# SH7_-_BROADCOM_ENCODER.net
KiCad netlist of a schematic drawn in Altium Designer
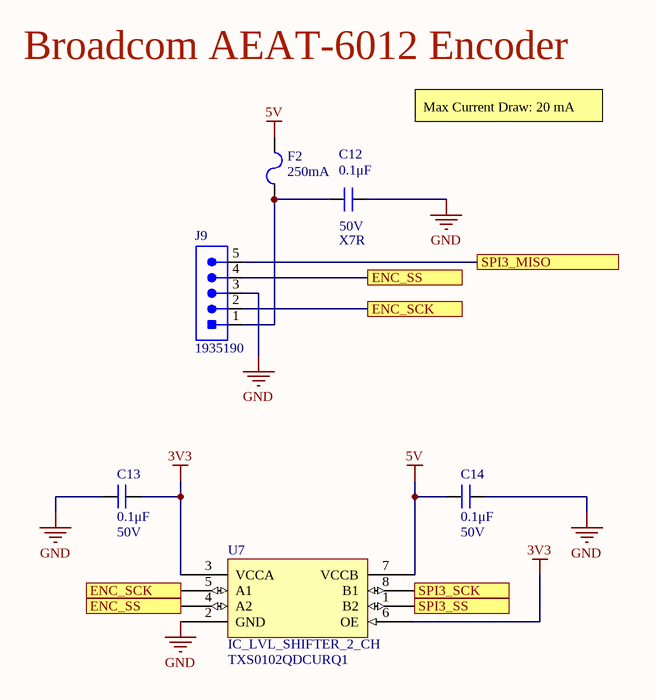
[diagram p0: SH7 - BROADCOM ENCODER.SchDoc]

(export (version "E")
  (design (tool "Eeschema 10.0.6"))
  (components
    (comp (ref "C12")
      (value "0.1μF")
      (footprint "CAP0603")
      (description "CAP CER 0.1UF 50V X7R 0603")
      (fields
        (field (name "DIELECTRIC") "X7R")
        (field (name "VOLTAGE RATING") "50V")
        (field (name "Comment") "CAP_0.1uF_50V_0603")
      )
      (libsource (lib "UWRT_Schematic_Library_2020") (part "CAP_0.1uF_50V_0603"))
    )
    (comp (ref "C13")
      (value "0.1μF")
      (footprint "CAP2012")
      (description "CAP CER 0.1UF 50V X7R 0805")
      (fields
        (field (name "LCSC PART #") "C49678")
        (field (name "VOLTAGE RATING") "50V")
        (field (name "Comment") "CAP_0.1uF_50V_0805")
      )
      (libsource (lib "UWRT_Schematic_Library_2020") (part "CAP_0.1uF_50V_0805"))
    )
    (comp (ref "C14")
      (value "0.1μF")
      (footprint "CAP2012")
      (description "CAP CER 0.1UF 50V X7R 0805")
      (fields
        (field (name "LCSC PART #") "C49678")
        (field (name "VOLTAGE RATING") "50V")
        (field (name "Comment") "CAP_0.1uF_50V_0805")
      )
      (libsource (lib "UWRT_Schematic_Library_2020") (part "CAP_0.1uF_50V_0805"))
    )
    (comp (ref "F2")
      (value "FUSE_250mA_0603")
      (footprint "FUSE_0603")
      (description "FUSE SMD 250mA 32V")
      (fields (field (name "CURRENT RATING") "250mA"))
      (libsource (lib "UWRT_Schematic_Library_2020") (part "FUSE_250mA_0603"))
    )
    (comp (ref "J9")
      (value "CON_5POS_SCREW_TERM")
      (footprint "1935190")
      (description "TERM BLK 5POS SIDE ENTRY 5MM")
      (fields (field (name "MANUFACTURER PART NUMBER 1") "1935190"))
      (libsource (lib "UWRT_Schematic_Library_2020") (part "CON_5POS_SCREW_TERM"))
    )
    (comp (ref "U7")
      (value "IC_LVL_SHIFTER_2_CH")
      (footprint "TXS0102QDCURQ1")
      (description "IC TRNSLTR BIDIRECTIONAL US8")
      (fields (field (name "MANUFACTURER PART NUMBER 1") "TXS0102QDCURQ1"))
      (libsource (lib "UWRT_Schematic_Library_2020") (part "IC_LVL_SHIFTER_2_CH"))
    )
  )
  (nets
    (net (code "1") (name "/ENC_SCK") (class "Default")
      (node (ref "J9") (pin "2") (pinfunction "2_2") (pintype "passive"))
      (node (ref "U7") (pin "5") (pinfunction "A1_5") (pintype "bidirectional"))
    )
    (net (code "2") (name "/ENC_SS") (class "Default")
      (node (ref "J9") (pin "4") (pinfunction "4_4") (pintype "passive"))
      (node (ref "U7") (pin "4") (pinfunction "A2_4") (pintype "bidirectional"))
    )
    (net (code "3") (name "/SPI3_MISO") (class "Default")
      (node (ref "J9") (pin "5") (pinfunction "5_5") (pintype "passive"))
    )
    (net (code "4") (name "/SPI3_SCK") (class "Default")
      (node (ref "U7") (pin "8") (pinfunction "B1_8") (pintype "bidirectional"))
    )
    (net (code "5") (name "/SPI3_SS") (class "Default")
      (node (ref "U7") (pin "1") (pinfunction "B2_1") (pintype "bidirectional"))
    )
    (net (code "6") (name "3V3") (class "Default")
      (node (ref "C13") (pin "2") (pinfunction "2_2") (pintype "passive"))
      (node (ref "U7") (pin "3") (pinfunction "VCCA_3") (pintype "power_in"))
      (node (ref "U7") (pin "6") (pinfunction "OE_6") (pintype "input"))
    )
    (net (code "7") (name "5V") (class "Default")
      (node (ref "C14") (pin "1") (pinfunction "1_1") (pintype "passive"))
      (node (ref "F2") (pin "2") (pinfunction "2_2") (pintype "passive"))
      (node (ref "U7") (pin "7") (pinfunction "VCCB_7") (pintype "power_in"))
    )
    (net (code "8") (name "GND") (class "Default")
      (node (ref "C12") (pin "1") (pinfunction "1_1") (pintype "passive"))
      (node (ref "C13") (pin "1") (pinfunction "1_1") (pintype "passive"))
      (node (ref "C14") (pin "2") (pinfunction "2_2") (pintype "passive"))
      (node (ref "J9") (pin "3") (pinfunction "3_3") (pintype "passive"))
      (node (ref "U7") (pin "2") (pinfunction "GND_2") (pintype "power_in"))
    )
    (net (code "9") (name "Net-(C12-Pad2)") (class "Default")
      (node (ref "C12") (pin "2") (pinfunction "2_2") (pintype "passive"))
      (node (ref "F2") (pin "1") (pinfunction "1_1") (pintype "passive"))
      (node (ref "J9") (pin "1") (pinfunction "1_1") (pintype "passive"))
    )
  )
)
